# laser-driver.net
KiCad netlist of a schematic drawn in EAGLE
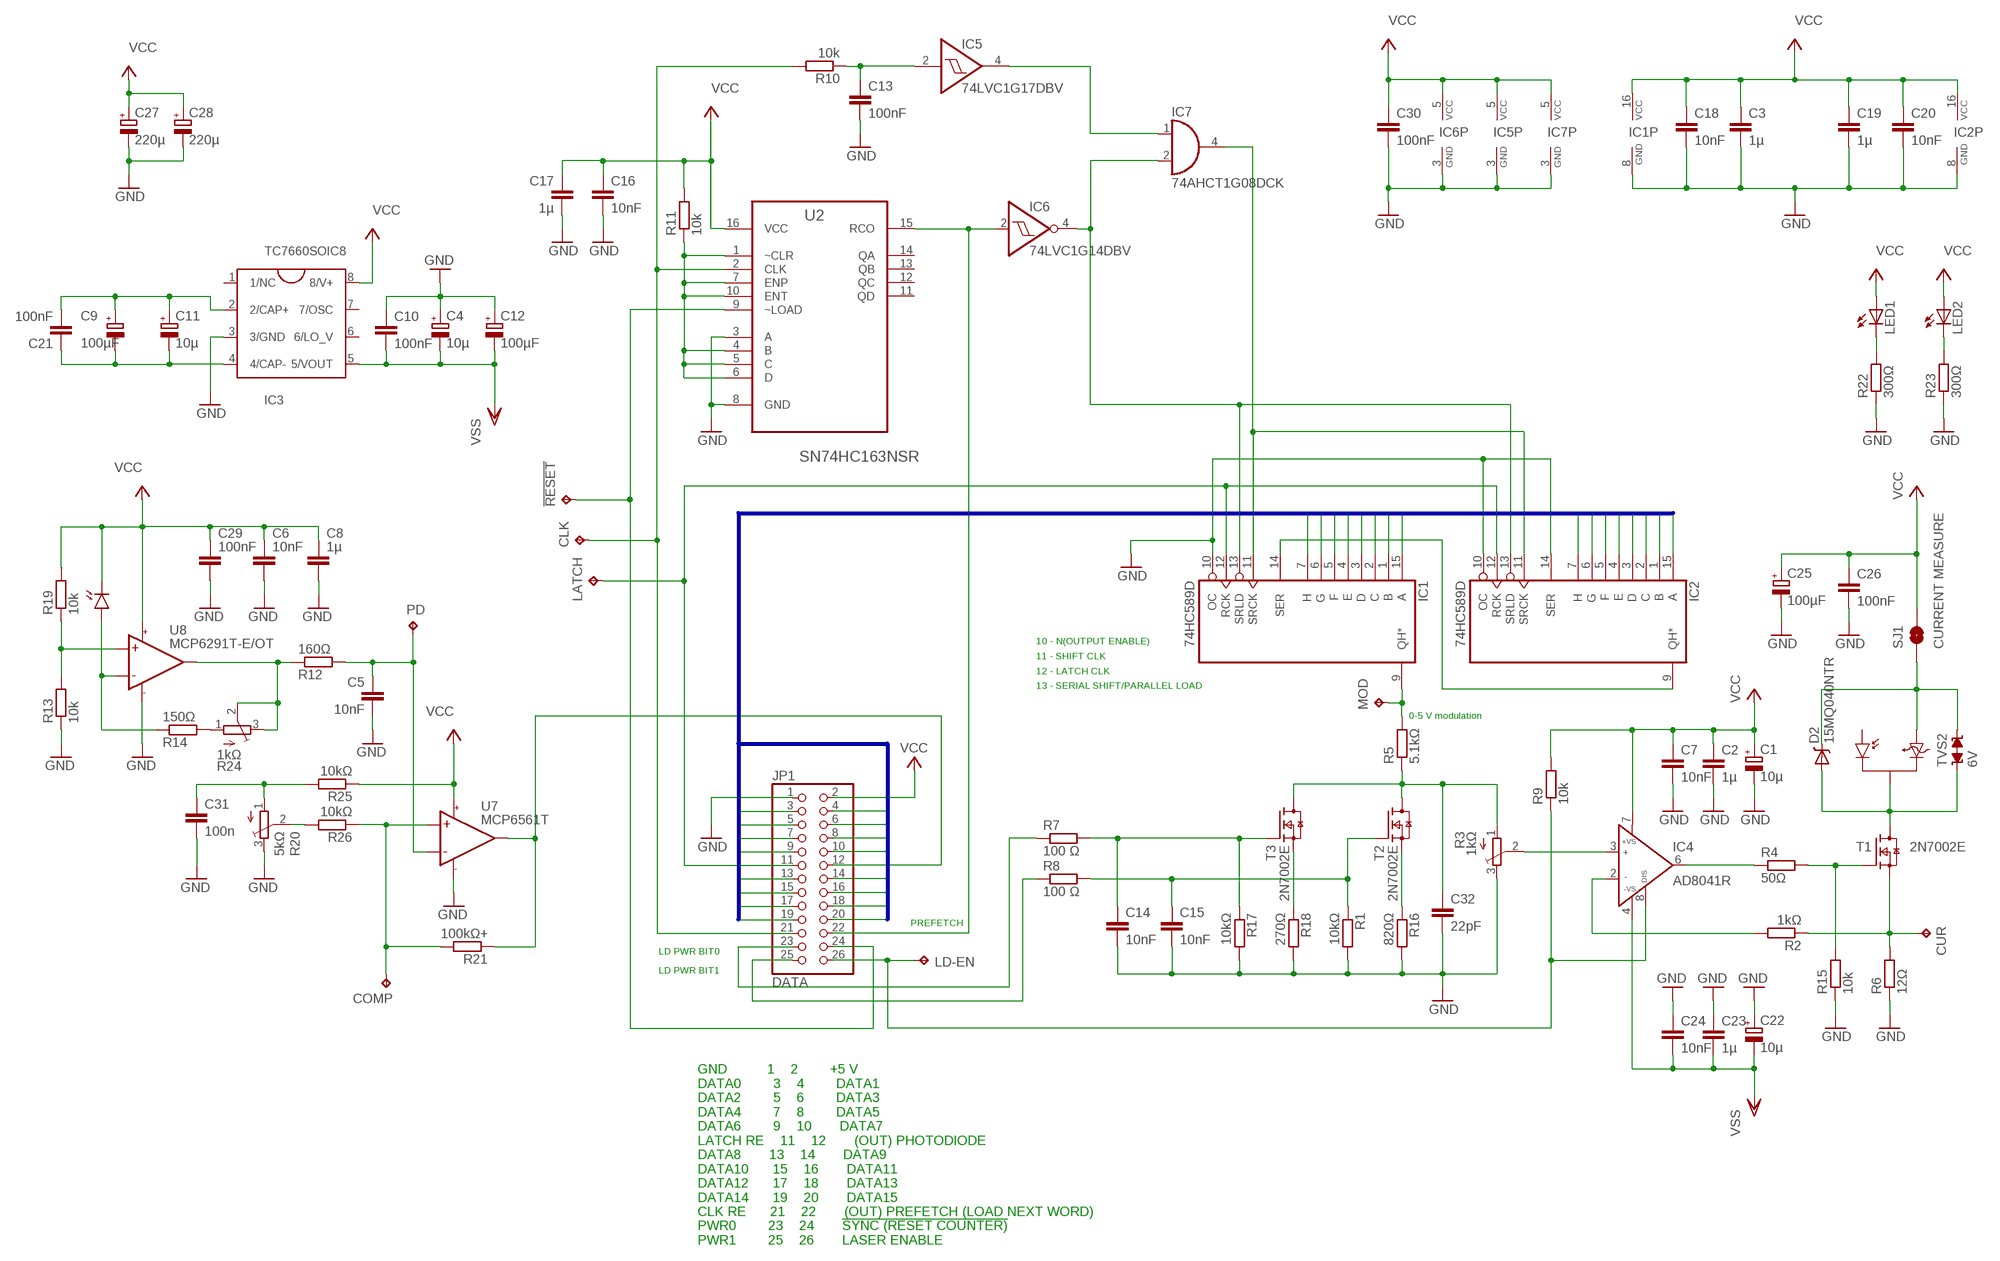
[diagram p0: schematic, sheet 1]

(export (version "E")
  (design (tool "Eeschema 10.0.6"))
  (components
    (comp (ref "!RESET")
      (value "TPB1,27")
      (footprint "eagle-import:B1,27")
      (libsource (lib "eagle-import") (part "TPB1,27"))
    )
    (comp (ref "C1")
      (value "10µ")
      (footprint "eagle-import:A_3216-18R")
      (libsource (lib "eagle-import") (part "CPOL-EUA/3216-18R"))
    )
    (comp (ref "C2")
      (value "1µ")
      (footprint "eagle-import:C1206")
      (libsource (lib "eagle-import") (part "C-EUC1206"))
    )
    (comp (ref "C3")
      (value "1µ")
      (footprint "eagle-import:C1206")
      (libsource (lib "eagle-import") (part "C-EUC1206"))
    )
    (comp (ref "C4")
      (value "10µ")
      (footprint "eagle-import:A_3216-18R")
      (libsource (lib "eagle-import") (part "CPOL-EUA/3216-18R"))
    )
    (comp (ref "C5")
      (value "10nF")
      (footprint "eagle-import:C0603")
      (libsource (lib "eagle-import") (part "C-EUC0603"))
    )
    (comp (ref "C6")
      (value "10nF")
      (footprint "eagle-import:C1206")
      (libsource (lib "eagle-import") (part "C-EUC1206"))
    )
    (comp (ref "C7")
      (value "10nF")
      (footprint "eagle-import:C1206")
      (libsource (lib "eagle-import") (part "C-EUC1206"))
    )
    (comp (ref "C8")
      (value "1µ")
      (footprint "eagle-import:C1206")
      (libsource (lib "eagle-import") (part "C-EUC1206"))
    )
    (comp (ref "C9")
      (value "100µF")
      (footprint "eagle-import:D_7343-31R")
      (libsource (lib "eagle-import") (part "CPOL-EUD/7343-31R"))
    )
    (comp (ref "C10")
      (value "100nF")
      (footprint "eagle-import:C1206")
      (libsource (lib "eagle-import") (part "C-EUC1206"))
    )
    (comp (ref "C11")
      (value "10µ")
      (footprint "eagle-import:A_3216-18R")
      (libsource (lib "eagle-import") (part "CPOL-EUA/3216-18R"))
    )
    (comp (ref "C12")
      (value "100µF")
      (footprint "eagle-import:D_7343-31R")
      (libsource (lib "eagle-import") (part "CPOL-EUD/7343-31R"))
    )
    (comp (ref "C13")
      (value "100nF")
      (footprint "eagle-import:C0603")
      (libsource (lib "eagle-import") (part "C-EUC0603"))
    )
    (comp (ref "C14")
      (value "10nF")
      (footprint "eagle-import:C1206")
      (libsource (lib "eagle-import") (part "C-EUC1206"))
    )
    (comp (ref "C15")
      (value "10nF")
      (footprint "eagle-import:C1206")
      (libsource (lib "eagle-import") (part "C-EUC1206"))
    )
    (comp (ref "C16")
      (value "10nF")
      (footprint "eagle-import:C1206")
      (libsource (lib "eagle-import") (part "C-EUC1206"))
    )
    (comp (ref "C17")
      (value "1µ")
      (footprint "eagle-import:C1206")
      (libsource (lib "eagle-import") (part "C-EUC1206"))
    )
    (comp (ref "C18")
      (value "10nF")
      (footprint "eagle-import:C1206")
      (libsource (lib "eagle-import") (part "C-EUC1206"))
    )
    (comp (ref "C19")
      (value "1µ")
      (footprint "eagle-import:C1206")
      (libsource (lib "eagle-import") (part "C-EUC1206"))
    )
    (comp (ref "C20")
      (value "10nF")
      (footprint "eagle-import:C1206")
      (libsource (lib "eagle-import") (part "C-EUC1206"))
    )
    (comp (ref "C21")
      (value "100nF")
      (footprint "eagle-import:C1206")
      (libsource (lib "eagle-import") (part "C-EUC1206"))
    )
    (comp (ref "C22")
      (value "10µ")
      (footprint "eagle-import:A_3216-18R")
      (libsource (lib "eagle-import") (part "CPOL-EUA/3216-18R"))
    )
    (comp (ref "C23")
      (value "1µ")
      (footprint "eagle-import:C1206")
      (libsource (lib "eagle-import") (part "C-EUC1206"))
    )
    (comp (ref "C24")
      (value "10nF")
      (footprint "eagle-import:C1206")
      (libsource (lib "eagle-import") (part "C-EUC1206"))
    )
    (comp (ref "C25")
      (value "100µF")
      (footprint "eagle-import:D_7343-31R")
      (libsource (lib "eagle-import") (part "CPOL-EUD/7343-31R"))
    )
    (comp (ref "C26")
      (value "100nF")
      (footprint "eagle-import:C0603")
      (libsource (lib "eagle-import") (part "C-EUC0603"))
    )
    (comp (ref "C27")
      (value "220µ")
      (footprint "eagle-import:153CLV-0605")
      (libsource (lib "eagle-import") (part "CPOL-EU153CLV-0605"))
    )
    (comp (ref "C28")
      (value "220µ")
      (footprint "eagle-import:153CLV-0605")
      (libsource (lib "eagle-import") (part "CPOL-EU153CLV-0605"))
    )
    (comp (ref "C29")
      (value "100nF")
      (footprint "eagle-import:C0603")
      (libsource (lib "eagle-import") (part "C-EUC0603"))
    )
    (comp (ref "C30")
      (value "100nF")
      (footprint "eagle-import:C0603")
      (libsource (lib "eagle-import") (part "C-EUC0603"))
    )
    (comp (ref "C31")
      (value "100n")
      (footprint "eagle-import:C0603")
      (libsource (lib "eagle-import") (part "C-EUC0603"))
    )
    (comp (ref "C32")
      (value "22pF")
      (footprint "eagle-import:C0603")
      (libsource (lib "eagle-import") (part "C-EUC0603"))
    )
    (comp (ref "CLK")
      (value "TPB1,27")
      (footprint "eagle-import:B1,27")
      (libsource (lib "eagle-import") (part "TPB1,27"))
    )
    (comp (ref "COMP")
      (value "TPB1,27")
      (footprint "eagle-import:B1,27")
      (libsource (lib "eagle-import") (part "TPB1,27"))
    )
    (comp (ref "CUR")
      (value "TPB1,27")
      (footprint "eagle-import:B1,27")
      (libsource (lib "eagle-import") (part "TPB1,27"))
    )
    (comp (ref "D2")
      (value "15MQ040NTR")
      (footprint "eagle-import:SMA-DIODE")
      (libsource (lib "eagle-import") (part "DIODE-SCHOTTKY_"))
    )
    (comp (ref "D3")
      (value "VTB8441BH")
      (footprint "eagle-import:VTB8441BH")
      (libsource (lib "eagle-import") (part "VTB8441BH"))
    )
    (comp (ref "IC1")
      (value "74HC589D")
      (footprint "eagle-import:SO16")
      (libsource (lib "eagle-import") (part "74589DHC"))
    )
    (comp (ref "IC2")
      (value "74HC589D")
      (footprint "eagle-import:SO16")
      (libsource (lib "eagle-import") (part "74589DHC"))
    )
    (comp (ref "IC3")
      (value "TC7660SOIC8")
      (footprint "eagle-import:SOIC8")
      (libsource (lib "eagle-import") (part "TC7660SOIC8"))
    )
    (comp (ref "IC4")
      (value "AD8041R")
      (footprint "eagle-import:SO8")
      (fields (field (name "MF") "ALTERA CORPORATION") (field (name "MPN") "AD8041ARZ"))
      (libsource (lib "eagle-import") (part "AD8041R"))
    )
    (comp (ref "IC5")
      (value "74LVC1G17DBV")
      (footprint "eagle-import:SOT23-5")
      (libsource (lib "eagle-import") (part "741G17DBVLVC"))
    )
    (comp (ref "IC6")
      (value "74LVC1G14DBV")
      (footprint "eagle-import:SOT23-5")
      (libsource (lib "eagle-import") (part "741G14DBVLVC"))
    )
    (comp (ref "IC7")
      (value "74AHCT1G08DCK")
      (footprint "eagle-import:SC70-5")
      (libsource (lib "eagle-import") (part "741G08DCKAHCT"))
    )
    (comp (ref "JP1")
      (value "DATA")
      (footprint "eagle-import:2X13")
      (libsource (lib "eagle-import") (part "PINHD-2X13"))
    )
    (comp (ref "LATCH")
      (value "TPB1,27")
      (footprint "eagle-import:B1,27")
      (libsource (lib "eagle-import") (part "TPB1,27"))
    )
    (comp (ref "LD-EN")
      (value "TPB1,27")
      (footprint "eagle-import:B1,27")
      (libsource (lib "eagle-import") (part "TPB1,27"))
    )
    (comp (ref "LED1")
      (value "LEDCHIPLED_0805")
      (footprint "eagle-import:CHIPLED_0805")
      (libsource (lib "eagle-import") (part "LEDCHIPLED_0805"))
    )
    (comp (ref "LED2")
      (value "LEDCHIPLED_0805")
      (footprint "eagle-import:CHIPLED_0805")
      (libsource (lib "eagle-import") (part "LEDCHIPLED_0805"))
    )
    (comp (ref "MOD")
      (value "TPB1,27")
      (footprint "eagle-import:B1,27")
      (libsource (lib "eagle-import") (part "TPB1,27"))
    )
    (comp (ref "PD")
      (value "TPB1,27")
      (footprint "eagle-import:B1,27")
      (libsource (lib "eagle-import") (part "TPB1,27"))
    )
    (comp (ref "R1")
      (value "10kΩ")
      (footprint "eagle-import:R0603")
      (libsource (lib "eagle-import") (part "R-EU_R0603"))
    )
    (comp (ref "R2")
      (value "1kΩ")
      (footprint "eagle-import:R0603")
      (libsource (lib "eagle-import") (part "R-EU_R0603"))
    )
    (comp (ref "R3")
      (value "1kΩ")
      (footprint "eagle-import:SM-42_43B")
      (libsource (lib "eagle-import") (part "TRIM_EU-SM-42/43B"))
    )
    (comp (ref "R4")
      (value "50Ω")
      (footprint "eagle-import:R0603")
      (libsource (lib "eagle-import") (part "R-EU_R0603"))
    )
    (comp (ref "R5")
      (value "5.1kΩ")
      (footprint "eagle-import:R0603")
      (libsource (lib "eagle-import") (part "R-EU_R0603"))
    )
    (comp (ref "R6")
      (value "12Ω")
      (footprint "eagle-import:R0603")
      (libsource (lib "eagle-import") (part "R-EU_R0603"))
    )
    (comp (ref "R7")
      (value "100 Ω")
      (footprint "eagle-import:R0603")
      (libsource (lib "eagle-import") (part "R-EU_R0603"))
    )
    (comp (ref "R8")
      (value "100 Ω")
      (footprint "eagle-import:R0603")
      (libsource (lib "eagle-import") (part "R-EU_R0603"))
    )
    (comp (ref "R9")
      (value "10k")
      (footprint "eagle-import:R0603")
      (libsource (lib "eagle-import") (part "R-EU_R0603"))
    )
    (comp (ref "R10")
      (value "10k")
      (footprint "eagle-import:R0603")
      (libsource (lib "eagle-import") (part "R-EU_R0603"))
    )
    (comp (ref "R11")
      (value "10k")
      (footprint "eagle-import:R0603")
      (libsource (lib "eagle-import") (part "R-EU_R0603"))
    )
    (comp (ref "R12")
      (value "160Ω")
      (footprint "eagle-import:R0603")
      (libsource (lib "eagle-import") (part "R-EU_R0603"))
    )
    (comp (ref "R13")
      (value "10k")
      (footprint "eagle-import:R0603")
      (libsource (lib "eagle-import") (part "R-EU_R0603"))
    )
    (comp (ref "R14")
      (value "150Ω")
      (footprint "eagle-import:R0603")
      (libsource (lib "eagle-import") (part "R-EU_R0603"))
    )
    (comp (ref "R15")
      (value "10k")
      (footprint "eagle-import:R0603")
      (libsource (lib "eagle-import") (part "R-EU_R0603"))
    )
    (comp (ref "R16")
      (value "820Ω")
      (footprint "eagle-import:R0603")
      (libsource (lib "eagle-import") (part "R-EU_R0603"))
    )
    (comp (ref "R17")
      (value "10kΩ")
      (footprint "eagle-import:R0603")
      (libsource (lib "eagle-import") (part "R-EU_R0603"))
    )
    (comp (ref "R18")
      (value "270Ω")
      (footprint "eagle-import:R0603")
      (libsource (lib "eagle-import") (part "R-EU_R0603"))
    )
    (comp (ref "R19")
      (value "10k")
      (footprint "eagle-import:R0603")
      (libsource (lib "eagle-import") (part "R-EU_R0603"))
    )
    (comp (ref "R20")
      (value "5kΩ")
      (footprint "eagle-import:SM-42_43B")
      (libsource (lib "eagle-import") (part "TRIM_EU-SM-42/43B"))
    )
    (comp (ref "R21")
      (value "100kΩ+")
      (footprint "eagle-import:R0603")
      (libsource (lib "eagle-import") (part "R-EU_R0603"))
    )
    (comp (ref "R22")
      (value "300Ω")
      (footprint "eagle-import:R0603")
      (libsource (lib "eagle-import") (part "R-EU_R0603"))
    )
    (comp (ref "R23")
      (value "300Ω")
      (footprint "eagle-import:R0603")
      (libsource (lib "eagle-import") (part "R-EU_R0603"))
    )
    (comp (ref "R24")
      (value "1kΩ")
      (footprint "eagle-import:3223G")
      (libsource (lib "eagle-import") (part "TRIM_EU-3223G"))
    )
    (comp (ref "R25")
      (value "10kΩ")
      (footprint "eagle-import:R0603")
      (libsource (lib "eagle-import") (part "R-EU_R0603"))
    )
    (comp (ref "R26")
      (value "10kΩ")
      (footprint "eagle-import:R0603")
      (libsource (lib "eagle-import") (part "R-EU_R0603"))
    )
    (comp (ref "SJ1")
      (value "CURRENT MEASURE")
      (footprint "eagle-import:SJ_2S-NO")
      (libsource (lib "eagle-import") (part "SOLDERJUMPERNO"))
    )
    (comp (ref "T1")
      (value "2N7002E")
      (footprint "eagle-import:SOT23")
      (libsource (lib "eagle-import") (part "2N7002E"))
    )
    (comp (ref "T2")
      (value "2N7002E")
      (footprint "eagle-import:SOT23")
      (libsource (lib "eagle-import") (part "2N7002E"))
    )
    (comp (ref "T3")
      (value "2N7002E")
      (footprint "eagle-import:SOT23")
      (libsource (lib "eagle-import") (part "2N7002E"))
    )
    (comp (ref "TVS2")
      (value "6V")
      (footprint "eagle-import:TVS0805")
      (libsource (lib "eagle-import") (part "TVS-0805"))
    )
    (comp (ref "U$1")
      (value "LASER-LED-COMMON-CATHODE")
      (footprint "eagle-import:TO-18")
      (libsource (lib "eagle-import") (part "LASER-LED-COMMON-CATHODE"))
    )
    (comp (ref "U2")
      (value "SN74HC163NSR")
      (footprint "eagle-import:SOIC127P780X200-16N")
      (libsource (lib "eagle-import") (part "SN74HC163NSR"))
    )
    (comp (ref "U7")
      (value "MCP6561T")
      (footprint "eagle-import:SOT23-5")
      (libsource (lib "eagle-import") (part "MCP6561T"))
    )
    (comp (ref "U8")
      (value "MCP6291T-E/OT")
      (footprint "eagle-import:SOT23-5")
      (libsource (lib "eagle-import") (part "MCP6291T-E/OT"))
    )
  )
  (nets
    (net (code "1") (name "/IN0") (class "Default")
      (node (ref "IC2") (pin "15") (pinfunction "A_15") (pintype "input"))
      (node (ref "JP1") (pin "3") (pinfunction "3_3") (pintype "passive"))
    )
    (net (code "2") (name "/IN1") (class "Default")
      (node (ref "IC2") (pin "1") (pinfunction "B_1") (pintype "input"))
      (node (ref "JP1") (pin "4") (pinfunction "4_4") (pintype "passive"))
    )
    (net (code "3") (name "/IN2") (class "Default")
      (node (ref "IC2") (pin "2") (pinfunction "C_2") (pintype "input"))
      (node (ref "JP1") (pin "5") (pinfunction "5_5") (pintype "passive"))
    )
    (net (code "4") (name "/IN3") (class "Default")
      (node (ref "IC2") (pin "3") (pinfunction "D_3") (pintype "input"))
      (node (ref "JP1") (pin "6") (pinfunction "6_6") (pintype "passive"))
    )
    (net (code "5") (name "/IN4") (class "Default")
      (node (ref "IC2") (pin "4") (pinfunction "E_4") (pintype "input"))
      (node (ref "JP1") (pin "7") (pinfunction "7_7") (pintype "passive"))
    )
    (net (code "6") (name "/IN5") (class "Default")
      (node (ref "IC2") (pin "5") (pinfunction "F_5") (pintype "input"))
      (node (ref "JP1") (pin "8") (pinfunction "8_8") (pintype "passive"))
    )
    (net (code "7") (name "/IN6") (class "Default")
      (node (ref "IC2") (pin "6") (pinfunction "G_6") (pintype "input"))
      (node (ref "JP1") (pin "9") (pinfunction "9_9") (pintype "passive"))
    )
    (net (code "8") (name "/IN7") (class "Default")
      (node (ref "IC2") (pin "7") (pinfunction "H_7") (pintype "input"))
      (node (ref "JP1") (pin "10") (pinfunction "10_10") (pintype "passive"))
    )
    (net (code "9") (name "/IN8") (class "Default")
      (node (ref "IC1") (pin "15") (pinfunction "A_15") (pintype "input"))
      (node (ref "JP1") (pin "13") (pinfunction "13_13") (pintype "passive"))
    )
    (net (code "10") (name "/IN9") (class "Default")
      (node (ref "IC1") (pin "1") (pinfunction "B_1") (pintype "input"))
      (node (ref "JP1") (pin "14") (pinfunction "14_14") (pintype "passive"))
    )
    (net (code "11") (name "/IN10") (class "Default")
      (node (ref "IC1") (pin "2") (pinfunction "C_2") (pintype "input"))
      (node (ref "JP1") (pin "15") (pinfunction "15_15") (pintype "passive"))
    )
    (net (code "12") (name "/IN11") (class "Default")
      (node (ref "IC1") (pin "3") (pinfunction "D_3") (pintype "input"))
      (node (ref "JP1") (pin "16") (pinfunction "16_16") (pintype "passive"))
    )
    (net (code "13") (name "/IN12") (class "Default")
      (node (ref "IC1") (pin "4") (pinfunction "E_4") (pintype "input"))
      (node (ref "JP1") (pin "17") (pinfunction "17_17") (pintype "passive"))
    )
    (net (code "14") (name "/IN13") (class "Default")
      (node (ref "IC1") (pin "5") (pinfunction "F_5") (pintype "input"))
      (node (ref "JP1") (pin "18") (pinfunction "18_18") (pintype "passive"))
    )
    (net (code "15") (name "/IN14") (class "Default")
      (node (ref "IC1") (pin "6") (pinfunction "G_6") (pintype "input"))
      (node (ref "JP1") (pin "19") (pinfunction "19_19") (pintype "passive"))
    )
    (net (code "16") (name "/IN15") (class "Default")
      (node (ref "IC1") (pin "7") (pinfunction "H_7") (pintype "input"))
      (node (ref "JP1") (pin "20") (pinfunction "20_20") (pintype "passive"))
    )
    (net (code "17") (name "GND") (class "Default")
      (node (ref "C1") (pin "-") (pinfunction "-_-") (pintype "passive"))
      (node (ref "C10") (pin "1") (pinfunction "1_1") (pintype "passive"))
      (node (ref "C12") (pin "+") (pinfunction "+_+") (pintype "passive"))
      (node (ref "C13") (pin "2") (pinfunction "2_2") (pintype "passive"))
      (node (ref "C14") (pin "2") (pinfunction "2_2") (pintype "passive"))
      (node (ref "C15") (pin "2") (pinfunction "2_2") (pintype "passive"))
      (node (ref "C16") (pin "2") (pinfunction "2_2") (pintype "passive"))
      (node (ref "C17") (pin "2") (pinfunction "2_2") (pintype "passive"))
      (node (ref "C18") (pin "2") (pinfunction "2_2") (pintype "passive"))
      (node (ref "C19") (pin "2") (pinfunction "2_2") (pintype "passive"))
      (node (ref "C2") (pin "2") (pinfunction "2_2") (pintype "passive"))
      (node (ref "C20") (pin "2") (pinfunction "2_2") (pintype "passive"))
      (node (ref "C22") (pin "+") (pinfunction "+_+") (pintype "passive"))
      (node (ref "C23") (pin "1") (pinfunction "1_1") (pintype "passive"))
      (node (ref "C24") (pin "1") (pinfunction "1_1") (pintype "passive"))
      (node (ref "C25") (pin "-") (pinfunction "-_-") (pintype "passive"))
      (node (ref "C26") (pin "2") (pinfunction "2_2") (pintype "passive"))
      (node (ref "C27") (pin "-") (pinfunction "-_-") (pintype "passive"))
      (node (ref "C28") (pin "-") (pinfunction "-_-") (pintype "passive"))
      (node (ref "C29") (pin "2") (pinfunction "2_2") (pintype "passive"))
      (node (ref "C3") (pin "2") (pinfunction "2_2") (pintype "passive"))
      (node (ref "C30") (pin "2") (pinfunction "2_2") (pintype "passive"))
      (node (ref "C31") (pin "2") (pinfunction "2_2") (pintype "passive"))
      (node (ref "C32") (pin "2") (pinfunction "2_2") (pintype "passive"))
      (node (ref "C4") (pin "+") (pinfunction "+_+") (pintype "passive"))
      (node (ref "C5") (pin "2") (pinfunction "2_2") (pintype "passive"))
      (node (ref "C6") (pin "2") (pinfunction "2_2") (pintype "passive"))
      (node (ref "C7") (pin "2") (pinfunction "2_2") (pintype "passive"))
      (node (ref "C8") (pin "2") (pinfunction "2_2") (pintype "passive"))
      (node (ref "IC1") (pin "10") (pinfunction "OC_10") (pintype "input"))
      (node (ref "IC1") (pin "8") (pinfunction "GND_8") (pintype "power_in"))
      (node (ref "IC2") (pin "10") (pinfunction "OC_10") (pintype "input"))
      (node (ref "IC2") (pin "14") (pinfunction "SER_14") (pintype "input"))
      (node (ref "IC2") (pin "8") (pinfunction "GND_8") (pintype "power_in"))
      (node (ref "IC3") (pin "3") (pinfunction "3/GND_3") (pintype "power_in"))
      (node (ref "IC5") (pin "3") (pinfunction "GND_3") (pintype "power_in"))
      (node (ref "IC6") (pin "3") (pinfunction "GND_3") (pintype "power_in"))
      (node (ref "IC7") (pin "3") (pinfunction "GND_3") (pintype "power_in"))
      (node (ref "JP1") (pin "1") (pinfunction "1_1") (pintype "passive"))
      (node (ref "R1") (pin "2") (pinfunction "2_2") (pintype "passive"))
      (node (ref "R13") (pin "1") (pinfunction "1_1") (pintype "passive"))
      (node (ref "R15") (pin "1") (pinfunction "1_1") (pintype "passive"))
      (node (ref "R16") (pin "2") (pinfunction "2_2") (pintype "passive"))
      (node (ref "R17") (pin "2") (pinfunction "2_2") (pintype "passive"))
      (node (ref "R18") (pin "2") (pinfunction "2_2") (pintype "passive"))
      (node (ref "R20") (pin "3") (pinfunction "E_3") (pintype "passive"))
      (node (ref "R22") (pin "1") (pinfunction "1_1") (pintype "passive"))
      (node (ref "R23") (pin "1") (pinfunction "1_1") (pintype "passive"))
      (node (ref "R3") (pin "3") (pinfunction "E_3") (pintype "passive"))
      (node (ref "R6") (pin "1") (pinfunction "1_1") (pintype "passive"))
      (node (ref "U2") (pin "3") (pinfunction "A_3") (pintype "input"))
      (node (ref "U2") (pin "8") (pinfunction "GND_8") (pintype "passive"))
      (node (ref "U7") (pin "2") (pinfunction "VCC-_2") (pintype "power_in"))
      (node (ref "U8") (pin "2") (pinfunction "VCC-_2") (pintype "power_in"))
    )
    (net (code "18") (name "Net-(D2-PadC)") (class "Default")
      (node (ref "D2") (pin "C") (pinfunction "C_C") (pintype "passive"))
      (node (ref "SJ1") (pin "1") (pinfunction "1_1") (pintype "passive"))
      (node (ref "TVS2") (pin "2") (pinfunction "2_2") (pintype "passive"))
      (node (ref "U$1") (pin "1") (pinfunction "1_1") (pintype "bidirectional"))
    )
    (net (code "19") (name "Net-(IC1A-QH*)") (class "Default")
      (node (ref "IC1") (pin "9") (pinfunction "QH*_9") (pintype "tri_state"))
      (node (ref "MOD") (pin "TP") (pinfunction "TP_TP") (pintype "input"))
      (node (ref "R5") (pin "2") (pinfunction "2_2") (pintype "passive"))
    )
    (net (code "20") (name "Net-(IC1A-RCK)") (class "Default")
      (node (ref "IC1") (pin "12") (pinfunction "RCK_12") (pintype "input"))
      (node (ref "IC2") (pin "12") (pinfunction "RCK_12") (pintype "input"))
      (node (ref "JP1") (pin "11") (pinfunction "11_11") (pintype "passive"))
      (node (ref "LATCH") (pin "TP") (pinfunction "TP_TP") (pintype "input"))
    )
    (net (code "21") (name "Net-(IC1A-SER)") (class "Default")
      (node (ref "IC1") (pin "14") (pinfunction "SER_14") (pintype "input"))
      (node (ref "IC2") (pin "9") (pinfunction "QH*_9") (pintype "tri_state"))
    )
    (net (code "22") (name "Net-(IC1A-SRCK)") (class "Default")
      (node (ref "IC1") (pin "11") (pinfunction "SRCK_11") (pintype "input"))
      (node (ref "IC2") (pin "11") (pinfunction "SRCK_11") (pintype "input"))
      (node (ref "IC7") (pin "4") (pinfunction "O_4") (pintype "output"))
    )
    (net (code "23") (name "Net-(IC1A-SRLD)") (class "Default")
      (node (ref "IC1") (pin "13") (pinfunction "SRLD_13") (pintype "input"))
      (node (ref "IC2") (pin "13") (pinfunction "SRLD_13") (pintype "input"))
      (node (ref "IC6") (pin "4") (pinfunction "O_4") (pintype "output"))
      (node (ref "IC7") (pin "2") (pinfunction "I1_2") (pintype "input"))
    )
    (net (code "24") (name "Net-(IC3-2{slash}CAP+)") (class "Default")
      (node (ref "C11") (pin "+") (pinfunction "+_+") (pintype "passive"))
      (node (ref "C21") (pin "2") (pinfunction "2_2") (pintype "passive"))
      (node (ref "C9") (pin "+") (pinfunction "+_+") (pintype "passive"))
      (node (ref "IC3") (pin "2") (pinfunction "2/CAP+_2") (pintype "bidirectional"))
    )
    (net (code "25") (name "Net-(IC3-4{slash}CAP-)") (class "Default")
      (node (ref "C11") (pin "-") (pinfunction "-_-") (pintype "passive"))
      (node (ref "C21") (pin "1") (pinfunction "1_1") (pintype "passive"))
      (node (ref "C9") (pin "-") (pinfunction "-_-") (pintype "passive"))
      (node (ref "IC3") (pin "4") (pinfunction "4/CAP-_4") (pintype "bidirectional"))
    )
    (net (code "26") (name "Net-(IC4-DISABLE)") (class "Default")
      (node (ref "IC4") (pin "8") (pinfunction "DISABLE_8") (pintype "passive"))
      (node (ref "JP1") (pin "26") (pinfunction "26_26") (pintype "passive"))
      (node (ref "LD-EN") (pin "TP") (pinfunction "TP_TP") (pintype "input"))
      (node (ref "R9") (pin "1") (pinfunction "1_1") (pintype "passive"))
    )
    (net (code "27") (name "Net-(IC4-IN+)") (class "Default")
      (node (ref "IC4") (pin "3") (pinfunction "IN+_3") (pintype "input"))
      (node (ref "R3") (pin "2") (pinfunction "S_2") (pintype "passive"))
    )
    (net (code "28") (name "Net-(IC4-IN-)") (class "Default")
      (node (ref "IC4") (pin "2") (pinfunction "IN-_2") (pintype "input"))
      (node (ref "R2") (pin "2") (pinfunction "2_2") (pintype "passive"))
    )
    (net (code "29") (name "Net-(IC4-OUT)") (class "Default")
      (node (ref "IC4") (pin "6") (pinfunction "OUT_6") (pintype "output"))
      (node (ref "R4") (pin "1") (pinfunction "1_1") (pintype "passive"))
    )
    (net (code "30") (name "Net-(IC5A-I)") (class "Default")
      (node (ref "C13") (pin "1") (pinfunction "1_1") (pintype "passive"))
      (node (ref "IC5") (pin "2") (pinfunction "I_2") (pintype "input"))
      (node (ref "R10") (pin "1") (pinfunction "1_1") (pintype "passive"))
    )
    (net (code "31") (name "Net-(IC5A-O)") (class "Default")
      (node (ref "IC5") (pin "4") (pinfunction "O_4") (pintype "output"))
      (node (ref "IC7") (pin "1") (pinfunction "I0_1") (pintype "input"))
    )
    (net (code "32") (name "Net-(IC6A-I)") (class "Default")
      (node (ref "IC6") (pin "2") (pinfunction "I_2") (pintype "input"))
      (node (ref "JP1") (pin "22") (pinfunction "22_22") (pintype "passive"))
      (node (ref "U2") (pin "15") (pinfunction "RCO_15") (pintype "output"))
    )
    (net (code "33") (name "Net-(JP1-Pad23)") (class "Default")
      (node (ref "JP1") (pin "23") (pinfunction "23_23") (pintype "passive"))
      (node (ref "R7") (pin "1") (pinfunction "1_1") (pintype "passive"))
    )
    (net (code "34") (name "Net-(JP1-Pad25)") (class "Default")
      (node (ref "JP1") (pin "25") (pinfunction "25_25") (pintype "passive"))
      (node (ref "R8") (pin "1") (pinfunction "1_1") (pintype "passive"))
    )
    (net (code "35") (name "Net-(LED1-PadC)") (class "Default")
      (node (ref "LED1") (pin "C") (pinfunction "C_C") (pintype "passive"))
      (node (ref "R22") (pin "2") (pinfunction "2_2") (pintype "passive"))
    )
    (net (code "36") (name "Net-(LED2-PadC)") (class "Default")
      (node (ref "LED2") (pin "C") (pinfunction "C_C") (pintype "passive"))
      (node (ref "R23") (pin "2") (pinfunction "2_2") (pintype "passive"))
    )
    (net (code "37") (name "Net-(R3-A)") (class "Default")
      (node (ref "C32") (pin "1") (pinfunction "1_1") (pintype "passive"))
      (node (ref "R3") (pin "1") (pinfunction "A_1") (pintype "passive"))
      (node (ref "R5") (pin "1") (pinfunction "1_1") (pintype "passive"))
      (node (ref "T2") (pin "3") (pinfunction "D_3") (pintype "passive"))
      (node (ref "T3") (pin "3") (pinfunction "D_3") (pintype "passive"))
    )
    (net (code "38") (name "Net-(R20-A)") (class "Default")
      (node (ref "C31") (pin "1") (pinfunction "1_1") (pintype "passive"))
      (node (ref "R20") (pin "1") (pinfunction "A_1") (pintype "passive"))
      (node (ref "R25") (pin "2") (pinfunction "2_2") (pintype "passive"))
    )
    (net (code "39") (name "Net-(R20-S)") (class "Default")
      (node (ref "R20") (pin "2") (pinfunction "S_2") (pintype "passive"))
      (node (ref "R26") (pin "2") (pinfunction "2_2") (pintype "passive"))
    )
    (net (code "40") (name "Net-(R24-A)") (class "Default")
      (node (ref "R14") (pin "2") (pinfunction "2_2") (pintype "passive"))
      (node (ref "R24") (pin "1") (pinfunction "A_1") (pintype "passive"))
    )
    (net (code "41") (name "Net-(R24-E)") (class "Default")
      (node (ref "R12") (pin "1") (pinfunction "1_1") (pintype "passive"))
      (node (ref "R24") (pin "2") (pinfunction "S_2") (pintype "passive"))
      (node (ref "R24") (pin "3") (pinfunction "E_3") (pintype "passive"))
      (node (ref "U8") (pin "1") (pinfunction "OUT_1") (pintype "output"))
    )
    (net (code "42") (name "Net-(T1-D)") (class "Default")
      (node (ref "D2") (pin "A") (pinfunction "A_A") (pintype "passive"))
      (node (ref "T1") (pin "3") (pinfunction "D_3") (pintype "passive"))
      (node (ref "TVS2") (pin "1") (pinfunction "1_1") (pintype "passive"))
      (node (ref "U$1") (pin "3") (pinfunction "3_3") (pintype "bidirectional"))
    )
    (net (code "43") (name "Net-(T1-G)") (class "Default")
      (node (ref "R15") (pin "2") (pinfunction "2_2") (pintype "passive"))
      (node (ref "R4") (pin "2") (pinfunction "2_2") (pintype "passive"))
      (node (ref "T1") (pin "1") (pinfunction "G_1") (pintype "passive"))
    )
    (net (code "44") (name "Net-(T1-S)") (class "Default")
      (node (ref "CUR") (pin "TP") (pinfunction "TP_TP") (pintype "input"))
      (node (ref "R2") (pin "1") (pinfunction "1_1") (pintype "passive"))
      (node (ref "R6") (pin "2") (pinfunction "2_2") (pintype "passive"))
      (node (ref "T1") (pin "2") (pinfunction "S_2") (pintype "passive"))
    )
    (net (code "45") (name "Net-(T2-G)") (class "Default")
      (node (ref "C15") (pin "1") (pinfunction "1_1") (pintype "passive"))
      (node (ref "R1") (pin "1") (pinfunction "1_1") (pintype "passive"))
      (node (ref "R8") (pin "2") (pinfunction "2_2") (pintype "passive"))
      (node (ref "T2") (pin "1") (pinfunction "G_1") (pintype "passive"))
    )
    (net (code "46") (name "Net-(T2-S)") (class "Default")
      (node (ref "R16") (pin "1") (pinfunction "1_1") (pintype "passive"))
      (node (ref "T2") (pin "2") (pinfunction "S_2") (pintype "passive"))
    )
    (net (code "47") (name "Net-(T3-G)") (class "Default")
      (node (ref "C14") (pin "1") (pinfunction "1_1") (pintype "passive"))
      (node (ref "R17") (pin "1") (pinfunction "1_1") (pintype "passive"))
      (node (ref "R7") (pin "2") (pinfunction "2_2") (pintype "passive"))
      (node (ref "T3") (pin "1") (pinfunction "G_1") (pintype "passive"))
    )
    (net (code "48") (name "Net-(T3-S)") (class "Default")
      (node (ref "R18") (pin "1") (pinfunction "1_1") (pintype "passive"))
      (node (ref "T3") (pin "2") (pinfunction "S_2") (pintype "passive"))
    )
    (net (code "49") (name "Net-(U2-B)") (class "Default")
      (node (ref "R11") (pin "1") (pinfunction "1_1") (pintype "passive"))
      (node (ref "U2") (pin "1") (pinfunction "~{CLR}_1") (pintype "input"))
      (node (ref "U2") (pin "10") (pinfunction "ENT_10") (pintype "input"))
      (node (ref "U2") (pin "4") (pinfunction "B_4") (pintype "input"))
      (node (ref "U2") (pin "5") (pinfunction "C_5") (pintype "input"))
      (node (ref "U2") (pin "6") (pinfunction "D_6") (pintype "input"))
      (node (ref "U2") (pin "7") (pinfunction "ENP_7") (pintype "input"))
    )
    (net (code "50") (name "Net-(U2-CLK)") (class "Default")
      (node (ref "CLK") (pin "TP") (pinfunction "TP_TP") (pintype "input"))
      (node (ref "JP1") (pin "21") (pinfunction "21_21") (pintype "passive"))
      (node (ref "R10") (pin "2") (pinfunction "2_2") (pintype "passive"))
      (node (ref "U2") (pin "2") (pinfunction "CLK_2") (pintype "input"))
    )
    (net (code "51") (name "Net-(U2-~{LOAD})") (class "Default")
      (node (ref "!RESET") (pin "TP") (pinfunction "TP_TP") (pintype "input"))
      (node (ref "JP1") (pin "24") (pinfunction "24_24") (pintype "passive"))
      (node (ref "U2") (pin "9") (pinfunction "~{LOAD}_9") (pintype "input"))
    )
    (net (code "52") (name "Net-(U7-IN+)") (class "Default")
      (node (ref "COMP") (pin "TP") (pinfunction "TP_TP") (pintype "input"))
      (node (ref "R21") (pin "2") (pinfunction "2_2") (pintype "passive"))
      (node (ref "R26") (pin "1") (pinfunction "1_1") (pintype "passive"))
      (node (ref "U7") (pin "3") (pinfunction "IN+_3") (pintype "input"))
    )
    (net (code "53") (name "Net-(U7-IN-)") (class "Default")
      (node (ref "C5") (pin "1") (pinfunction "1_1") (pintype "passive"))
      (node (ref "PD") (pin "TP") (pinfunction "TP_TP") (pintype "input"))
      (node (ref "R12") (pin "2") (pinfunction "2_2") (pintype "passive"))
      (node (ref "U7") (pin "4") (pinfunction "IN-_4") (pintype "input"))
    )
    (net (code "54") (name "Net-(U7-OUT)") (class "Default")
      (node (ref "JP1") (pin "12") (pinfunction "12_12") (pintype "passive"))
      (node (ref "R21") (pin "1") (pinfunction "1_1") (pintype "passive"))
      (node (ref "U7") (pin "1") (pinfunction "OUT_1") (pintype "output"))
    )
    (net (code "55") (name "Net-(U8-IN+)") (class "Default")
      (node (ref "R13") (pin "2") (pinfunction "2_2") (pintype "passive"))
      (node (ref "R19") (pin "1") (pinfunction "1_1") (pintype "passive"))
      (node (ref "U8") (pin "3") (pinfunction "IN+_3") (pintype "input"))
    )
    (net (code "56") (name "Net-(U8-IN-)") (class "Default")
      (node (ref "D3") (pin "A") (pinfunction "A_A") (pintype "bidirectional"))
      (node (ref "R14") (pin "1") (pinfunction "1_1") (pintype "passive"))
      (node (ref "U8") (pin "4") (pinfunction "IN-_4") (pintype "input"))
    )
    (net (code "57") (name "VCC") (class "Default")
      (node (ref "C1") (pin "+") (pinfunction "+_+") (pintype "passive"))
      (node (ref "C16") (pin "1") (pinfunction "1_1") (pintype "passive"))
      (node (ref "C17") (pin "1") (pinfunction "1_1") (pintype "passive"))
      (node (ref "C18") (pin "1") (pinfunction "1_1") (pintype "passive"))
      (node (ref "C19") (pin "1") (pinfunction "1_1") (pintype "passive"))
      (node (ref "C2") (pin "1") (pinfunction "1_1") (pintype "passive"))
      (node (ref "C20") (pin "1") (pinfunction "1_1") (pintype "passive"))
      (node (ref "C25") (pin "+") (pinfunction "+_+") (pintype "passive"))
      (node (ref "C26") (pin "1") (pinfunction "1_1") (pintype "passive"))
      (node (ref "C27") (pin "+") (pinfunction "+_+") (pintype "passive"))
      (node (ref "C28") (pin "+") (pinfunction "+_+") (pintype "passive"))
      (node (ref "C29") (pin "1") (pinfunction "1_1") (pintype "passive"))
      (node (ref "C3") (pin "1") (pinfunction "1_1") (pintype "passive"))
      (node (ref "C30") (pin "1") (pinfunction "1_1") (pintype "passive"))
      (node (ref "C6") (pin "1") (pinfunction "1_1") (pintype "passive"))
      (node (ref "C7") (pin "1") (pinfunction "1_1") (pintype "passive"))
      (node (ref "C8") (pin "1") (pinfunction "1_1") (pintype "passive"))
      (node (ref "D3") (pin "K") (pinfunction "K_K") (pintype "bidirectional"))
      (node (ref "IC1") (pin "16") (pinfunction "VCC_16") (pintype "power_in"))
      (node (ref "IC2") (pin "16") (pinfunction "VCC_16") (pintype "power_in"))
      (node (ref "IC3") (pin "8") (pinfunction "8/V+_8") (pintype "power_in"))
      (node (ref "IC4") (pin "7") (pinfunction "+VS_7") (pintype "input"))
      (node (ref "IC5") (pin "5") (pinfunction "VCC_5") (pintype "power_in"))
      (node (ref "IC6") (pin "5") (pinfunction "VCC_5") (pintype "power_in"))
      (node (ref "IC7") (pin "5") (pinfunction "VCC_5") (pintype "power_in"))
      (node (ref "JP1") (pin "2") (pinfunction "2_2") (pintype "passive"))
      (node (ref "LED1") (pin "A") (pinfunction "A_A") (pintype "passive"))
      (node (ref "LED2") (pin "A") (pinfunction "A_A") (pintype "passive"))
      (node (ref "R11") (pin "2") (pinfunction "2_2") (pintype "passive"))
      (node (ref "R19") (pin "2") (pinfunction "2_2") (pintype "passive"))
      (node (ref "R25") (pin "1") (pinfunction "1_1") (pintype "passive"))
      (node (ref "R9") (pin "2") (pinfunction "2_2") (pintype "passive"))
      (node (ref "SJ1") (pin "2") (pinfunction "2_2") (pintype "passive"))
      (node (ref "U2") (pin "16") (pinfunction "VCC_16") (pintype "power_in"))
      (node (ref "U7") (pin "5") (pinfunction "VCC+_5") (pintype "power_in"))
      (node (ref "U8") (pin "5") (pinfunction "VCC+_5") (pintype "power_in"))
    )
    (net (code "58") (name "VSS") (class "Default")
      (node (ref "C10") (pin "2") (pinfunction "2_2") (pintype "passive"))
      (node (ref "C12") (pin "-") (pinfunction "-_-") (pintype "passive"))
      (node (ref "C22") (pin "-") (pinfunction "-_-") (pintype "passive"))
      (node (ref "C23") (pin "2") (pinfunction "2_2") (pintype "passive"))
      (node (ref "C24") (pin "2") (pinfunction "2_2") (pintype "passive"))
      (node (ref "C4") (pin "-") (pinfunction "-_-") (pintype "passive"))
      (node (ref "IC3") (pin "5") (pinfunction "5/VOUT_5") (pintype "output"))
      (node (ref "IC4") (pin "4") (pinfunction "-VS_4") (pintype "input"))
    )
    (net (code "59") (name "unconnected-(IC3-1{slash}NC-Pad1)") (class "Default")
      (node (ref "IC3") (pin "1") (pinfunction "1/NC_1") (pintype "no_connect"))
    )
    (net (code "60") (name "unconnected-(IC3-6{slash}LO_V-Pad6)") (class "Default")
      (node (ref "IC3") (pin "6") (pinfunction "6/LO_V_6") (pintype "bidirectional"))
    )
    (net (code "61") (name "unconnected-(IC3-7{slash}OSC-Pad7)") (class "Default")
      (node (ref "IC3") (pin "7") (pinfunction "7/OSC_7") (pintype "bidirectional"))
    )
    (net (code "62") (name "unconnected-(U$1-Pad2)") (class "Default")
      (node (ref "U$1") (pin "2") (pinfunction "2_2") (pintype "bidirectional"))
    )
    (net (code "63") (name "unconnected-(U2-QA-Pad14)") (class "Default")
      (node (ref "U2") (pin "14") (pinfunction "QA_14") (pintype "output"))
    )
    (net (code "64") (name "unconnected-(U2-QB-Pad13)") (class "Default")
      (node (ref "U2") (pin "13") (pinfunction "QB_13") (pintype "output"))
    )
    (net (code "65") (name "unconnected-(U2-QC-Pad12)") (class "Default")
      (node (ref "U2") (pin "12") (pinfunction "QC_12") (pintype "output"))
    )
    (net (code "66") (name "unconnected-(U2-QD-Pad11)") (class "Default")
      (node (ref "U2") (pin "11") (pinfunction "QD_11") (pintype "output"))
    )
  )
)
